# DAPule-LPC11U35-v1_0_0.net
KiCad netlist of a schematic drawn in EAGLE
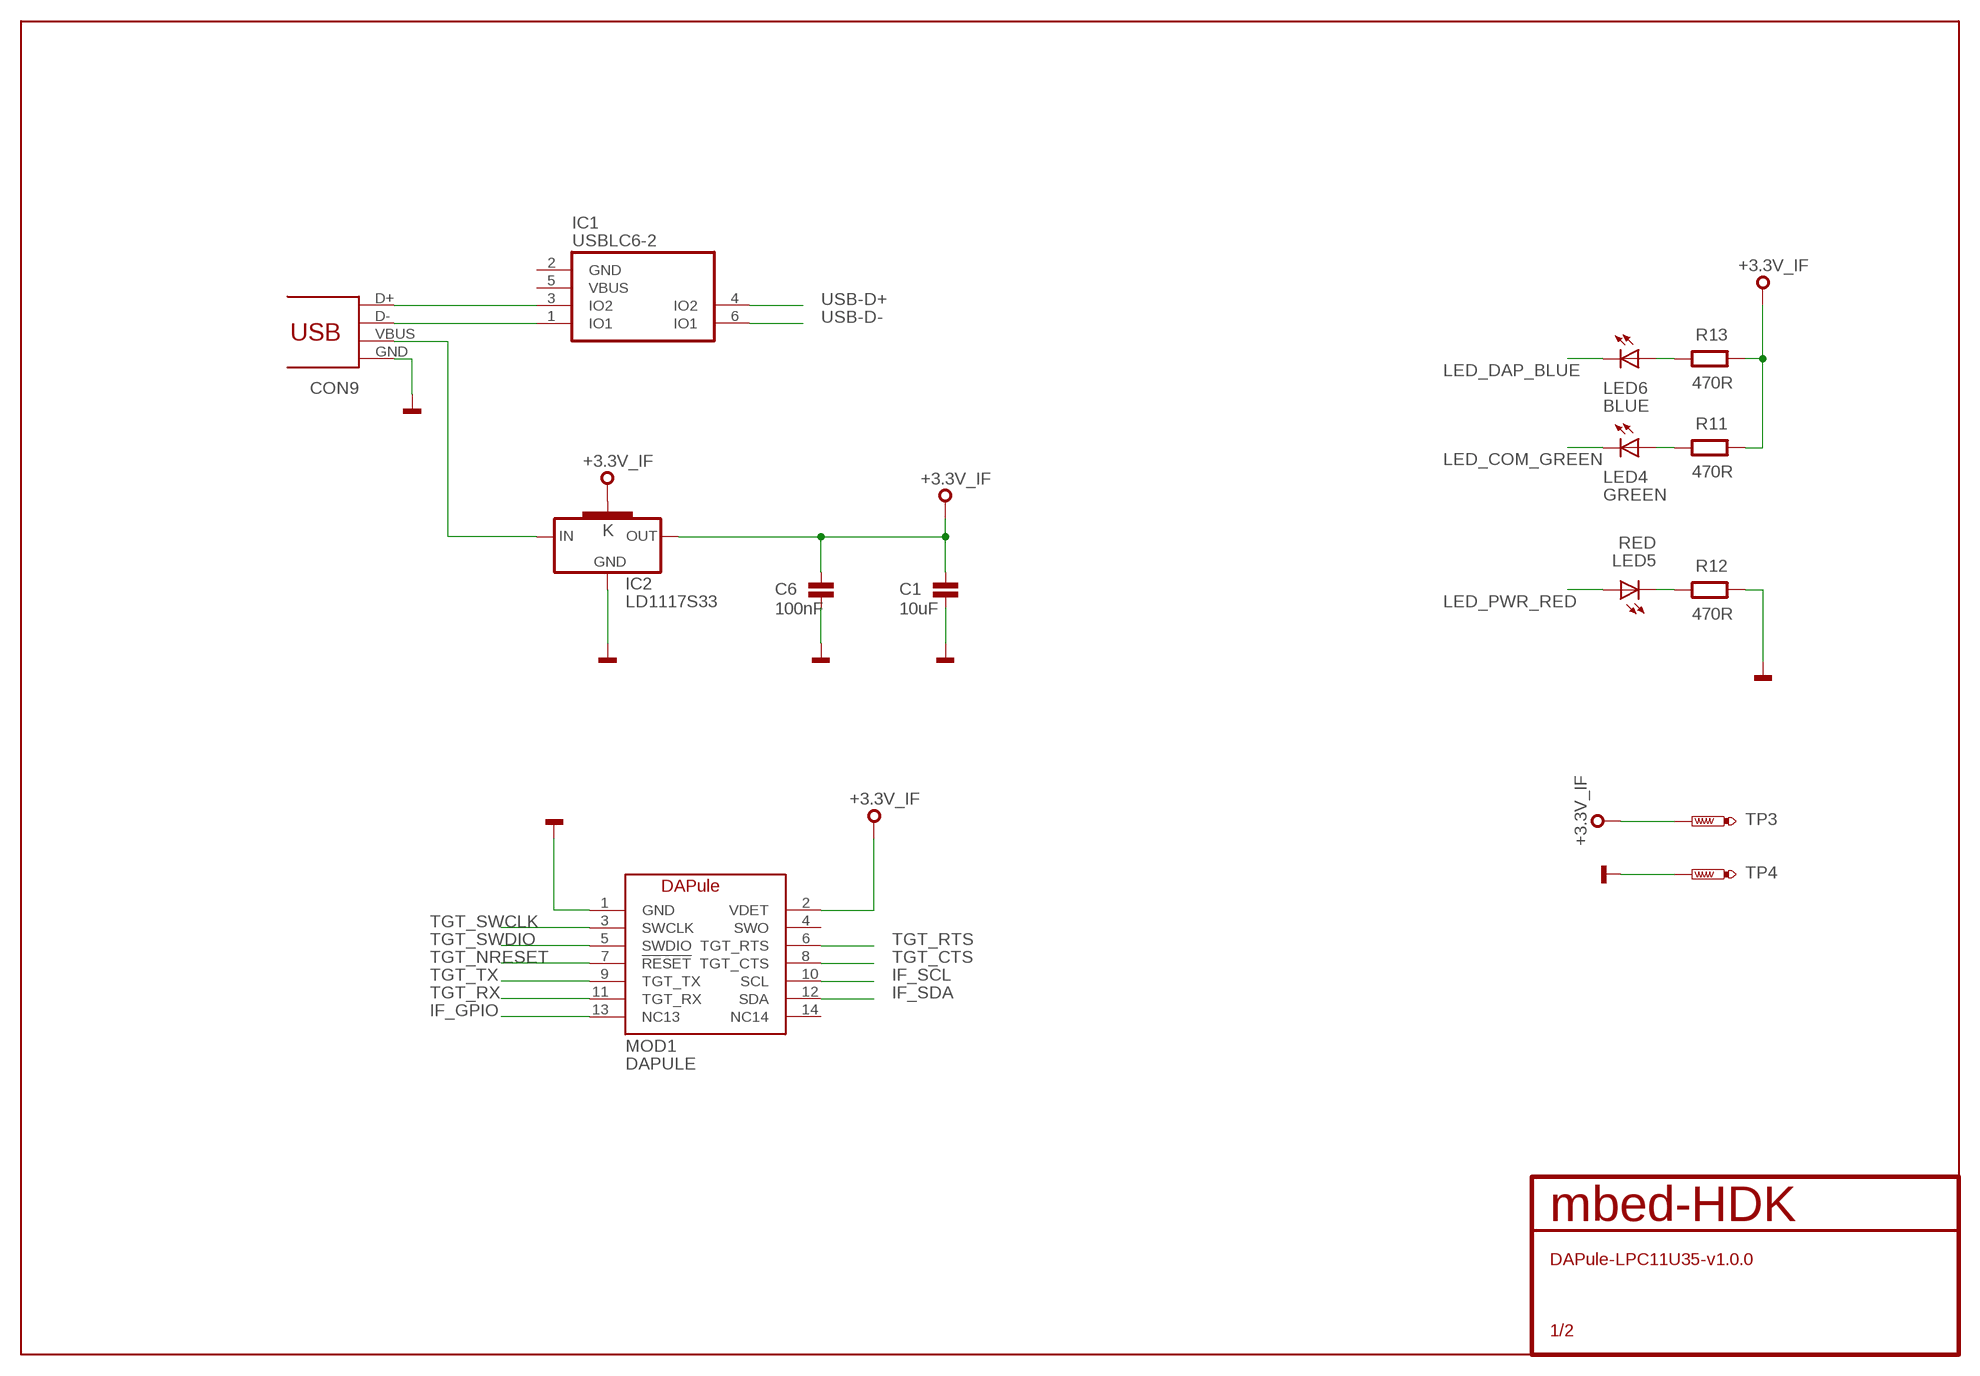
[diagram p0: schematic, sheet 1]
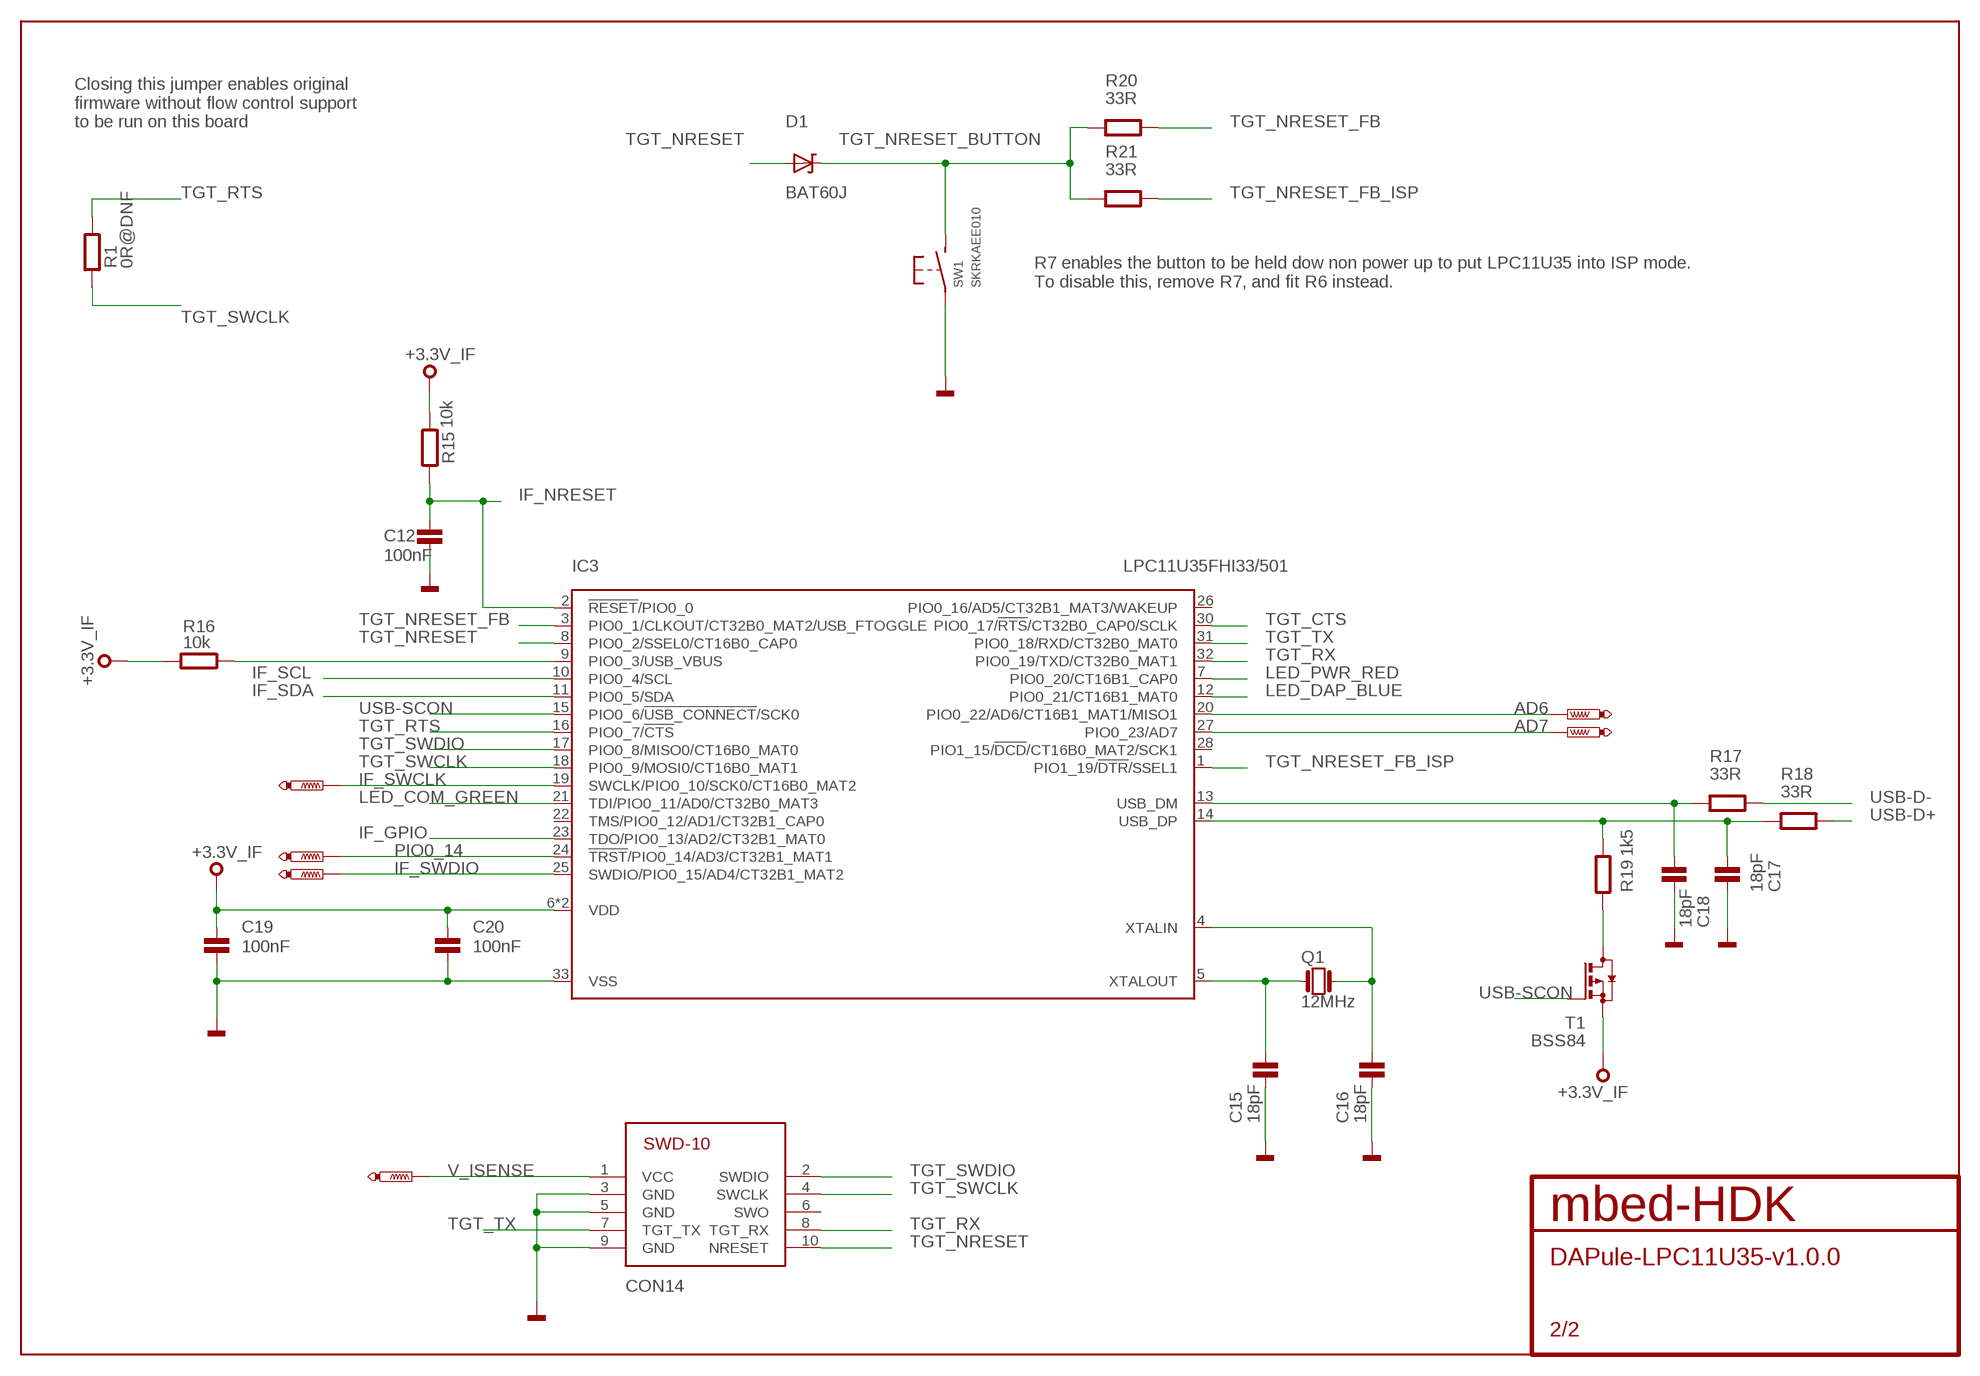
[diagram p1: schematic, sheet 2]

(export (version "E")
  (design (tool "Eeschema 10.0.6"))
  (components
    (comp (ref "C1")
      (value "10uF")
      (footprint "eagle-import:0603")
      (libsource (lib "eagle-import") (part "C0603"))
    )
    (comp (ref "C6")
      (value "100nF")
      (footprint "eagle-import:0603")
      (libsource (lib "eagle-import") (part "C0603"))
    )
    (comp (ref "CON9")
      (value "USB_MICROB")
      (footprint "eagle-import:MOLEX-47364-0001")
      (libsource (lib "eagle-import") (part "USB_MICROB"))
    )
    (comp (ref "IC1")
      (value "USBLC6-2SC6")
      (footprint "eagle-import:SOT23-6L")
      (libsource (lib "eagle-import") (part "USBLC6-2SC6"))
    )
    (comp (ref "IC2")
      (value "LD1117S33")
      (footprint "eagle-import:SOT223")
      (libsource (lib "eagle-import") (part "LD1117S33"))
    )
    (comp (ref "LED4")
      (value "GREEN")
      (footprint "eagle-import:CHIPLED_0603")
      (libsource (lib "eagle-import") (part "LED0603"))
    )
    (comp (ref "LED5")
      (value "RED")
      (footprint "eagle-import:CHIPLED_0603")
      (libsource (lib "eagle-import") (part "LED0603"))
    )
    (comp (ref "LED6")
      (value "BLUE")
      (footprint "eagle-import:CHIPLED_0603")
      (libsource (lib "eagle-import") (part "LED0603"))
    )
    (comp (ref "MOD1")
      (value "DAPULE")
      (footprint "eagle-import:DAPULE")
      (libsource (lib "eagle-import") (part "DAPULE"))
    )
    (comp (ref "R11")
      (value "470R")
      (footprint "eagle-import:0603@1")
      (libsource (lib "eagle-import") (part "R0603"))
    )
    (comp (ref "R12")
      (value "470R")
      (footprint "eagle-import:0603@1")
      (libsource (lib "eagle-import") (part "R0603"))
    )
    (comp (ref "R13")
      (value "470R")
      (footprint "eagle-import:0603@1")
      (libsource (lib "eagle-import") (part "R0603"))
    )
    (comp (ref "TP3")
      (value "TEST-POINT-50R-PTH")
      (footprint "eagle-import:TP50-PTH")
      (libsource (lib "eagle-import") (part "TEST-POINT-50R-PTH"))
    )
    (comp (ref "TP4")
      (value "TEST-POINT-50R-PTH")
      (footprint "eagle-import:TP50-PTH")
      (libsource (lib "eagle-import") (part "TEST-POINT-50R-PTH"))
    )
    (comp (ref "C12")
      (value "100nF")
      (footprint "eagle-import:0603")
      (libsource (lib "eagle-import") (part "C0603"))
    )
    (comp (ref "C15")
      (value "18pF")
      (footprint "eagle-import:0603")
      (libsource (lib "eagle-import") (part "C0603"))
    )
    (comp (ref "C16")
      (value "18pF")
      (footprint "eagle-import:0603")
      (libsource (lib "eagle-import") (part "C0603"))
    )
    (comp (ref "C17")
      (value "18pF")
      (footprint "eagle-import:0603")
      (libsource (lib "eagle-import") (part "C0603"))
    )
    (comp (ref "C18")
      (value "18pF")
      (footprint "eagle-import:0603")
      (libsource (lib "eagle-import") (part "C0603"))
    )
    (comp (ref "C19")
      (value "100nF")
      (footprint "eagle-import:0603")
      (libsource (lib "eagle-import") (part "C0603"))
    )
    (comp (ref "C20")
      (value "100nF")
      (footprint "eagle-import:0603")
      (libsource (lib "eagle-import") (part "C0603"))
    )
    (comp (ref "CON14")
      (value "SWD-10/TC2050_SMD")
      (footprint "eagle-import:FTSH-105-02")
      (libsource (lib "eagle-import") (part "SWD-10/TC2050_SMD"))
    )
    (comp (ref "D1")
      (value "BAT60J")
      (footprint "eagle-import:BAT60A")
      (libsource (lib "eagle-import") (part "BAT60A"))
    )
    (comp (ref "IC3")
      (value "LPC11U35FHI33/501")
      (footprint "eagle-import:SOT617-3")
      (libsource (lib "eagle-import") (part "LPC11U35FHI33/501"))
    )
    (comp (ref "Q1")
      (value "12MHz")
      (footprint "eagle-import:3.2X.2.5")
      (libsource (lib "eagle-import") (part "Q_3.2X2.5"))
    )
    (comp (ref "R1")
      (value "0R@DNF")
      (footprint "eagle-import:0402@1")
      (libsource (lib "eagle-import") (part "R0402"))
    )
    (comp (ref "R15")
      (value "10k")
      (footprint "eagle-import:0603@1")
      (libsource (lib "eagle-import") (part "R0603"))
    )
    (comp (ref "R16")
      (value "10k")
      (footprint "eagle-import:0603@1")
      (libsource (lib "eagle-import") (part "R0603"))
    )
    (comp (ref "R17")
      (value "33R")
      (footprint "eagle-import:0603@1")
      (libsource (lib "eagle-import") (part "R0603"))
    )
    (comp (ref "R18")
      (value "33R")
      (footprint "eagle-import:0603@1")
      (libsource (lib "eagle-import") (part "R0603"))
    )
    (comp (ref "R19")
      (value "1k5")
      (footprint "eagle-import:0603@1")
      (libsource (lib "eagle-import") (part "R0603"))
    )
    (comp (ref "R20")
      (value "33R")
      (footprint "eagle-import:0603@1")
      (libsource (lib "eagle-import") (part "R0603"))
    )
    (comp (ref "R21")
      (value "33R")
      (footprint "eagle-import:0603@1")
      (libsource (lib "eagle-import") (part "R0603"))
    )
    (comp (ref "SW1")
      (value "SKRKAEE010")
      (footprint "eagle-import:SKRKAEE010")
      (fields (field (name "MF") "ALPS"))
      (libsource (lib "eagle-import") (part "SKRKAEE010"))
    )
    (comp (ref "T1")
      (value "BSS84")
      (footprint "eagle-import:SOT23")
      (libsource (lib "eagle-import") (part "BSS84"))
    )
    (comp (ref "TP1")
      (value "PTR1TP16R")
      (footprint "eagle-import:TP16R")
      (libsource (lib "eagle-import") (part "PTR1TP16R"))
    )
    (comp (ref "TP8")
      (value "PTR1TP07R")
      (footprint "eagle-import:TP07R")
      (libsource (lib "eagle-import") (part "PTR1TP07R"))
    )
    (comp (ref "TP9")
      (value "PTR1TP07R")
      (footprint "eagle-import:TP07R")
      (libsource (lib "eagle-import") (part "PTR1TP07R"))
    )
    (comp (ref "TP11")
      (value "PTR1TP07R")
      (footprint "eagle-import:TP07R")
      (libsource (lib "eagle-import") (part "PTR1TP07R"))
    )
    (comp (ref "TP12")
      (value "PTR1TP07R")
      (footprint "eagle-import:TP07R")
      (libsource (lib "eagle-import") (part "PTR1TP07R"))
    )
    (comp (ref "TP13")
      (value "PTR1TP07R")
      (footprint "eagle-import:TP07R")
      (libsource (lib "eagle-import") (part "PTR1TP07R"))
    )
  )
  (nets
    (net (code "1") (name "+3.3V_IF") (class "Default")
      (node (ref "C1") (pin "1") (pinfunction "P$1_1") (pintype "passive"))
      (node (ref "C19") (pin "1") (pinfunction "P$1_1") (pintype "passive"))
      (node (ref "C20") (pin "1") (pinfunction "P$1_1") (pintype "passive"))
      (node (ref "C6") (pin "1") (pinfunction "P$1_1") (pintype "passive"))
      (node (ref "IC2") (pin "2") (pinfunction "OUT_2") (pintype "passive"))
      (node (ref "IC2") (pin "4") (pinfunction "K_4") (pintype "passive"))
      (node (ref "IC3") (pin "29") (pinfunction "VDD_29") (pintype "passive"))
      (node (ref "IC3") (pin "6") (pinfunction "VDD_6") (pintype "passive"))
      (node (ref "MOD1") (pin "2") (pinfunction "VDET_2") (pintype "bidirectional"))
      (node (ref "R11") (pin "1") (pinfunction "P$1_1") (pintype "passive"))
      (node (ref "R13") (pin "1") (pinfunction "P$1_1") (pintype "passive"))
      (node (ref "R15") (pin "2") (pinfunction "P$2_2") (pintype "passive"))
      (node (ref "R16") (pin "2") (pinfunction "P$2_2") (pintype "passive"))
      (node (ref "T1") (pin "2") (pinfunction "S_2") (pintype "passive"))
      (node (ref "TP3") (pin "TP") (pinfunction "TP_TP") (pintype "input"))
    )
    (net (code "2") (name "AD6") (class "Default")
      (node (ref "IC3") (pin "20") (pinfunction "PIO0_22/AD6/CT16B1_MAT1/MISO1_20") (pintype "bidirectional"))
      (node (ref "TP9") (pin "TP") (pinfunction "TP_TP") (pintype "input"))
    )
    (net (code "3") (name "AD7") (class "Default")
      (node (ref "IC3") (pin "27") (pinfunction "PIO0_23/AD7_27") (pintype "bidirectional"))
      (node (ref "TP8") (pin "TP") (pinfunction "TP_TP") (pintype "input"))
    )
    (net (code "4") (name "GND") (class "Default")
      (node (ref "C1") (pin "2") (pinfunction "P$2_2") (pintype "passive"))
      (node (ref "C12") (pin "2") (pinfunction "P$2_2") (pintype "passive"))
      (node (ref "C15") (pin "2") (pinfunction "P$2_2") (pintype "passive"))
      (node (ref "C16") (pin "2") (pinfunction "P$2_2") (pintype "passive"))
      (node (ref "C17") (pin "2") (pinfunction "P$2_2") (pintype "passive"))
      (node (ref "C18") (pin "2") (pinfunction "P$2_2") (pintype "passive"))
      (node (ref "C19") (pin "2") (pinfunction "P$2_2") (pintype "passive"))
      (node (ref "C20") (pin "2") (pinfunction "P$2_2") (pintype "passive"))
      (node (ref "C6") (pin "2") (pinfunction "P$2_2") (pintype "passive"))
      (node (ref "CON14") (pin "3") (pinfunction "GND_3") (pintype "bidirectional"))
      (node (ref "CON14") (pin "5") (pinfunction "GND_5") (pintype "bidirectional"))
      (node (ref "CON14") (pin "9") (pinfunction "GND_9") (pintype "bidirectional"))
      (node (ref "CON9") (pin "GND") (pinfunction "GND_GND") (pintype "bidirectional"))
      (node (ref "IC2") (pin "1") (pinfunction "GND_1") (pintype "input"))
      (node (ref "IC3") (pin "33") (pinfunction "VSS_33") (pintype "passive"))
      (node (ref "MOD1") (pin "1") (pinfunction "GND_1") (pintype "bidirectional"))
      (node (ref "R12") (pin "1") (pinfunction "P$1_1") (pintype "passive"))
      (node (ref "SW1") (pin "P$1") (pinfunction "P_P$1") (pintype "passive"))
      (node (ref "TP4") (pin "TP") (pinfunction "TP_TP") (pintype "input"))
    )
    (net (code "5") (name "IF_GPIO") (class "Default")
      (node (ref "IC3") (pin "23") (pinfunction "TDO/PIO0_13/AD2/CT32B1_MAT0_23") (pintype "bidirectional"))
      (node (ref "MOD1") (pin "13") (pinfunction "NC13_13") (pintype "bidirectional"))
    )
    (net (code "6") (name "IF_NRESET") (class "Default")
      (node (ref "C12") (pin "1") (pinfunction "P$1_1") (pintype "passive"))
      (node (ref "IC3") (pin "2") (pinfunction "~{RESET}/PIO0_0_2") (pintype "bidirectional"))
      (node (ref "R15") (pin "1") (pinfunction "P$1_1") (pintype "passive"))
    )
    (net (code "7") (name "IF_SCL") (class "Default")
      (node (ref "IC3") (pin "10") (pinfunction "PIO0_4/SCL_10") (pintype "bidirectional"))
      (node (ref "MOD1") (pin "10") (pinfunction "SCL_10") (pintype "bidirectional"))
    )
    (net (code "8") (name "IF_SDA") (class "Default")
      (node (ref "IC3") (pin "11") (pinfunction "PIO0_5/SDA_11") (pintype "bidirectional"))
      (node (ref "MOD1") (pin "12") (pinfunction "SDA_12") (pintype "bidirectional"))
    )
    (net (code "9") (name "IF_SWCLK") (class "Default")
      (node (ref "IC3") (pin "19") (pinfunction "SWCLK/PIO0_10/SCK0/CT16B0_MAT2_19") (pintype "bidirectional"))
      (node (ref "TP12") (pin "TP") (pinfunction "TP_TP") (pintype "input"))
    )
    (net (code "10") (name "IF_SWDIO") (class "Default")
      (node (ref "IC3") (pin "25") (pinfunction "SWDIO/PIO0_15/AD4/CT32B1_MAT2_25") (pintype "bidirectional"))
      (node (ref "TP11") (pin "TP") (pinfunction "TP_TP") (pintype "input"))
    )
    (net (code "11") (name "LED_COM_GREEN") (class "Default")
      (node (ref "IC3") (pin "21") (pinfunction "TDI/PIO0_11/AD0/CT32B0_MAT3_21") (pintype "bidirectional"))
      (node (ref "LED4") (pin "C") (pinfunction "C_C") (pintype "passive"))
    )
    (net (code "12") (name "LED_DAP_BLUE") (class "Default")
      (node (ref "IC3") (pin "12") (pinfunction "PIO0_21/CT16B1_MAT0_12") (pintype "bidirectional"))
      (node (ref "LED6") (pin "C") (pinfunction "C_C") (pintype "passive"))
    )
    (net (code "13") (name "LED_PWR_RED") (class "Default")
      (node (ref "IC3") (pin "7") (pinfunction "PIO0_20/CT16B1_CAP0_7") (pintype "bidirectional"))
      (node (ref "LED5") (pin "A") (pinfunction "A_A") (pintype "passive"))
    )
    (net (code "14") (name "Net-(C15-P$1)") (class "Default")
      (node (ref "C15") (pin "1") (pinfunction "P$1_1") (pintype "passive"))
      (node (ref "IC3") (pin "5") (pinfunction "XTALOUT_5") (pintype "output"))
      (node (ref "Q1") (pin "P$1") (pinfunction "1_P$1") (pintype "passive"))
    )
    (net (code "15") (name "Net-(C16-P$1)") (class "Default")
      (node (ref "C16") (pin "1") (pinfunction "P$1_1") (pintype "passive"))
      (node (ref "IC3") (pin "4") (pinfunction "XTALIN_4") (pintype "input"))
      (node (ref "Q1") (pin "P$3") (pinfunction "2_P$3") (pintype "passive"))
    )
    (net (code "16") (name "Net-(C17-P$1)") (class "Default")
      (node (ref "C17") (pin "1") (pinfunction "P$1_1") (pintype "passive"))
      (node (ref "IC3") (pin "14") (pinfunction "USB_DP_14") (pintype "bidirectional"))
      (node (ref "R18") (pin "2") (pinfunction "P$2_2") (pintype "passive"))
      (node (ref "R19") (pin "2") (pinfunction "P$2_2") (pintype "passive"))
    )
    (net (code "17") (name "Net-(C18-P$1)") (class "Default")
      (node (ref "C18") (pin "1") (pinfunction "P$1_1") (pintype "passive"))
      (node (ref "IC3") (pin "13") (pinfunction "USB_DM_13") (pintype "bidirectional"))
      (node (ref "R17") (pin "2") (pinfunction "P$2_2") (pintype "passive"))
    )
    (net (code "18") (name "Net-(CON9-PadD+)") (class "Default")
      (node (ref "CON9") (pin "D+") (pinfunction "D+_D+") (pintype "bidirectional"))
      (node (ref "IC1") (pin "3") (pinfunction "IO2_3") (pintype "bidirectional"))
    )
    (net (code "19") (name "Net-(CON9-PadD-)") (class "Default")
      (node (ref "CON9") (pin "D-") (pinfunction "D-_D-") (pintype "bidirectional"))
      (node (ref "IC1") (pin "1") (pinfunction "IO1_1") (pintype "bidirectional"))
    )
    (net (code "20") (name "Net-(IC2-IN)") (class "Default")
      (node (ref "CON9") (pin "VBUS") (pinfunction "VBUS_VBUS") (pintype "bidirectional"))
      (node (ref "IC2") (pin "3") (pinfunction "IN_3") (pintype "input"))
    )
    (net (code "21") (name "Net-(IC3-PIO0_3{slash}USB_VBUS)") (class "Default")
      (node (ref "IC3") (pin "9") (pinfunction "PIO0_3/USB_VBUS_9") (pintype "bidirectional"))
      (node (ref "R16") (pin "1") (pinfunction "P$1_1") (pintype "passive"))
    )
    (net (code "22") (name "Net-(R11-P$2)") (class "Default")
      (node (ref "LED4") (pin "A") (pinfunction "A_A") (pintype "passive"))
      (node (ref "R11") (pin "2") (pinfunction "P$2_2") (pintype "passive"))
    )
    (net (code "23") (name "Net-(R12-P$2)") (class "Default")
      (node (ref "LED5") (pin "C") (pinfunction "C_C") (pintype "passive"))
      (node (ref "R12") (pin "2") (pinfunction "P$2_2") (pintype "passive"))
    )
    (net (code "24") (name "Net-(R13-P$2)") (class "Default")
      (node (ref "LED6") (pin "A") (pinfunction "A_A") (pintype "passive"))
      (node (ref "R13") (pin "2") (pinfunction "P$2_2") (pintype "passive"))
    )
    (net (code "25") (name "Net-(R19-P$1)") (class "Default")
      (node (ref "R19") (pin "1") (pinfunction "P$1_1") (pintype "passive"))
      (node (ref "T1") (pin "3") (pinfunction "D_3") (pintype "passive"))
    )
    (net (code "26") (name "PIO0_14") (class "Default")
      (node (ref "IC3") (pin "24") (pinfunction "~{TRST}/PIO0_14/AD3/CT32B1_MAT1_24") (pintype "bidirectional"))
      (node (ref "TP13") (pin "TP") (pinfunction "TP_TP") (pintype "input"))
    )
    (net (code "27") (name "TGT_CTS") (class "Default")
      (node (ref "IC3") (pin "30") (pinfunction "PIO0_17/~{RTS}/CT32B0_CAP0/SCLK_30") (pintype "bidirectional"))
      (node (ref "MOD1") (pin "8") (pinfunction "TGT_CTS_8") (pintype "bidirectional"))
    )
    (net (code "28") (name "TGT_NRESET") (class "Default")
      (node (ref "CON14") (pin "10") (pinfunction "NRESET_10") (pintype "bidirectional"))
      (node (ref "D1") (pin "A") (pinfunction "A_A") (pintype "passive"))
      (node (ref "IC3") (pin "8") (pinfunction "PIO0_2/SSEL0/CT16B0_CAP0_8") (pintype "bidirectional"))
      (node (ref "MOD1") (pin "7") (pinfunction "~{RESET}_7") (pintype "bidirectional"))
    )
    (net (code "29") (name "TGT_NRESET_BUTTON") (class "Default")
      (node (ref "D1") (pin "K") (pinfunction "K_K") (pintype "passive"))
      (node (ref "R20") (pin "2") (pinfunction "P$2_2") (pintype "passive"))
      (node (ref "R21") (pin "2") (pinfunction "P$2_2") (pintype "passive"))
      (node (ref "SW1") (pin "P$2") (pinfunction "S_P$2") (pintype "passive"))
    )
    (net (code "30") (name "TGT_NRESET_FB") (class "Default")
      (node (ref "IC3") (pin "3") (pinfunction "PIO0_1/CLKOUT/CT32B0_MAT2/USB_FTOGGLE_3") (pintype "bidirectional"))
      (node (ref "R20") (pin "1") (pinfunction "P$1_1") (pintype "passive"))
    )
    (net (code "31") (name "TGT_NRESET_FB_ISP") (class "Default")
      (node (ref "IC3") (pin "1") (pinfunction "PIO1_19/~{DTR}/SSEL1_1") (pintype "bidirectional"))
      (node (ref "R21") (pin "1") (pinfunction "P$1_1") (pintype "passive"))
    )
    (net (code "32") (name "TGT_RTS") (class "Default")
      (node (ref "IC3") (pin "16") (pinfunction "PIO0_7/~{CTS}_16") (pintype "bidirectional"))
      (node (ref "MOD1") (pin "6") (pinfunction "TGT_RTS_6") (pintype "bidirectional"))
      (node (ref "R1") (pin "2") (pinfunction "P$2_2") (pintype "passive"))
    )
    (net (code "33") (name "TGT_RX") (class "Default")
      (node (ref "CON14") (pin "8") (pinfunction "TGT_RX_8") (pintype "bidirectional"))
      (node (ref "IC3") (pin "32") (pinfunction "PIO0_19/TXD/CT32B0_MAT1_32") (pintype "bidirectional"))
      (node (ref "MOD1") (pin "11") (pinfunction "TGT_RX_11") (pintype "bidirectional"))
    )
    (net (code "34") (name "TGT_SWCLK") (class "Default")
      (node (ref "CON14") (pin "4") (pinfunction "SWCLK_4") (pintype "bidirectional"))
      (node (ref "IC3") (pin "18") (pinfunction "PIO0_9/MOSI0/CT16B0_MAT1_18") (pintype "bidirectional"))
      (node (ref "MOD1") (pin "3") (pinfunction "SWCLK_3") (pintype "bidirectional"))
      (node (ref "R1") (pin "1") (pinfunction "P$1_1") (pintype "passive"))
    )
    (net (code "35") (name "TGT_SWDIO") (class "Default")
      (node (ref "CON14") (pin "2") (pinfunction "SWDIO_2") (pintype "bidirectional"))
      (node (ref "IC3") (pin "17") (pinfunction "PIO0_8/MISO0/CT16B0_MAT0_17") (pintype "bidirectional"))
      (node (ref "MOD1") (pin "5") (pinfunction "SWDIO_5") (pintype "bidirectional"))
    )
    (net (code "36") (name "TGT_TX") (class "Default")
      (node (ref "CON14") (pin "7") (pinfunction "TGT_TX_7") (pintype "bidirectional"))
      (node (ref "IC3") (pin "31") (pinfunction "PIO0_18/RXD/CT32B0_MAT0_31") (pintype "bidirectional"))
      (node (ref "MOD1") (pin "9") (pinfunction "TGT_TX_9") (pintype "bidirectional"))
    )
    (net (code "37") (name "USB-D+") (class "Default")
      (node (ref "IC1") (pin "4") (pinfunction "IO2_4") (pintype "bidirectional"))
      (node (ref "R18") (pin "1") (pinfunction "P$1_1") (pintype "passive"))
    )
    (net (code "38") (name "USB-D-") (class "Default")
      (node (ref "IC1") (pin "6") (pinfunction "IO1_6") (pintype "bidirectional"))
      (node (ref "R17") (pin "1") (pinfunction "P$1_1") (pintype "passive"))
    )
    (net (code "39") (name "USB-SCON") (class "Default")
      (node (ref "IC3") (pin "15") (pinfunction "PIO0_6/~{USB_CONNECT}/SCK0_15") (pintype "bidirectional"))
      (node (ref "T1") (pin "1") (pinfunction "G_1") (pintype "passive"))
    )
    (net (code "40") (name "V_ISENSE") (class "Default")
      (node (ref "CON14") (pin "1") (pinfunction "VCC_1") (pintype "bidirectional"))
      (node (ref "TP1") (pin "TP") (pinfunction "TP_TP") (pintype "input"))
    )
    (net (code "41") (name "unconnected-(CON14-SWO-Pad6)") (class "Default")
      (node (ref "CON14") (pin "6") (pinfunction "SWO_6") (pintype "bidirectional"))
    )
    (net (code "42") (name "unconnected-(IC1-GND-Pad2)") (class "Default")
      (node (ref "IC1") (pin "2") (pinfunction "GND_2") (pintype "bidirectional"))
    )
    (net (code "43") (name "unconnected-(IC1-VBUS-Pad5)") (class "Default")
      (node (ref "IC1") (pin "5") (pinfunction "VBUS_5") (pintype "bidirectional"))
    )
    (net (code "44") (name "unconnected-(IC3-PIO0_16{slash}AD5{slash}CT32B1_MAT3{slash}WAKEUP-Pad26)") (class "Default")
      (node (ref "IC3") (pin "26") (pinfunction "PIO0_16/AD5/CT32B1_MAT3/WAKEUP_26") (pintype "bidirectional"))
    )
    (net (code "45") (name "unconnected-(IC3-PIO1_15{slash}~{DCD}{slash}CT16B0_MAT2{slash}SCK1-Pad28)") (class "Default")
      (node (ref "IC3") (pin "28") (pinfunction "PIO1_15/~{DCD}/CT16B0_MAT2/SCK1_28") (pintype "bidirectional"))
    )
    (net (code "46") (name "unconnected-(IC3-TMS{slash}PIO0_12{slash}AD1{slash}CT32B1_CAP0-Pad22)") (class "Default")
      (node (ref "IC3") (pin "22") (pinfunction "TMS/PIO0_12/AD1/CT32B1_CAP0_22") (pintype "bidirectional"))
    )
    (net (code "47") (name "unconnected-(MOD1-NC14-Pad14)") (class "Default")
      (node (ref "MOD1") (pin "14") (pinfunction "NC14_14") (pintype "bidirectional"))
    )
    (net (code "48") (name "unconnected-(MOD1-SWO-Pad4)") (class "Default")
      (node (ref "MOD1") (pin "4") (pinfunction "SWO_4") (pintype "bidirectional"))
    )
  )
)
